# 3763.net
KiCad netlist of a schematic drawn in Altium Designer
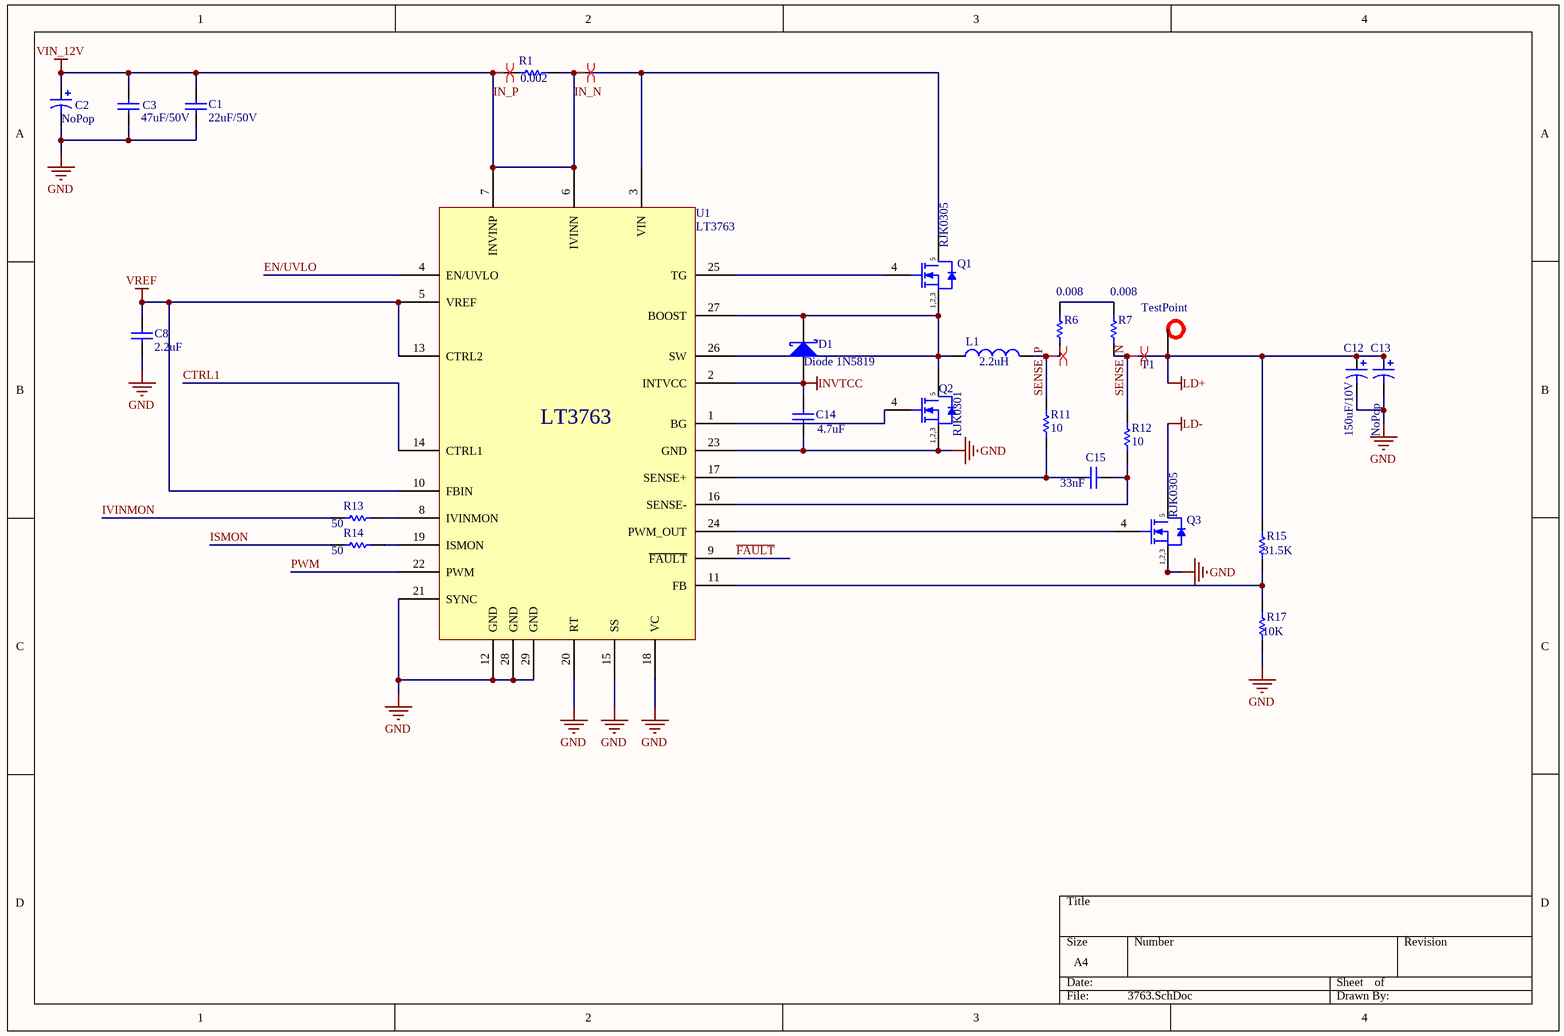
[diagram p0: 3763.SchDoc]

(export (version "E")
  (design (tool "Eeschema 10.0.6"))
  (components
    (comp (ref "C1")
      (value "22uF/50V")
      (footprint "1206[3216] - NP")
      (description "Capacitor")
      (fields (field (name "PUBLISHER") "Altium Limited"))
      (libsource (lib "Miscellaneous Devices") (part "Cap"))
    )
    (comp (ref "C2")
      (value "NoPop")
      (footprint "SMC_Altium Capacity 8*10")
      (description "Altium Electrolytic Cap")
      (fields (field (name "PUBLISHER") "Altium Limited"))
      (libsource (lib "Miscellaneous Devices") (part "Cap Pol1"))
    )
    (comp (ref "C3")
      (value "47uF/50V")
      (footprint "1206[3216] - NP")
      (description "Capacitor")
      (fields (field (name "PUBLISHER") "Altium Limited"))
      (libsource (lib "Miscellaneous Devices") (part "Cap"))
    )
    (comp (ref "C8")
      (value "2.2uF")
      (footprint "1608[0603]")
      (description "Capacitor")
      (fields (field (name "PUBLISHER") "Altium Limited"))
      (libsource (lib "Miscellaneous Devices") (part "Cap"))
    )
    (comp (ref "C12")
      (value "150uF/10V")
      (footprint "Laser-LiuXin:7343")
      (description "Tantum Cap")
      (fields (field (name "PUBLISHER") "Altium Limited"))
      (libsource (lib "Miscellaneous Devices") (part "Cap Pol1"))
    )
    (comp (ref "C13")
      (value "NoPop")
      (footprint "SMC_Altium Capacity 8*10")
      (description "Altium Electrolytic Cap")
      (fields (field (name "PUBLISHER") "Altium Limited"))
      (libsource (lib "Miscellaneous Devices") (part "Cap Pol1"))
    )
    (comp (ref "C14")
      (value "4.7uF")
      (footprint "1608[0603]")
      (description "Capacitor")
      (fields (field (name "PUBLISHER") "Altium Limited"))
      (libsource (lib "Miscellaneous Devices") (part "Cap"))
    )
    (comp (ref "C15")
      (value "33nF")
      (footprint "1608[0603]")
      (description "Capacitor")
      (fields (field (name "PUBLISHER") "Altium Limited"))
      (libsource (lib "Miscellaneous Devices") (part "Cap"))
    )
    (comp (ref "D1")
      (value "Diode 1N5819")
      (footprint "SMA")
      (description "Schottky Diode")
      (fields (field (name "PUBLISHER") "Altium Limited"))
      (libsource (lib "Miscellaneous Devices") (part "D Schottky"))
    )
    (comp (ref "L1")
      (value "2.2uH")
      (footprint "IHLP4040")
      (description "Inductor")
      (fields (field (name "Comment") "Inductor,2.2uH") (field (name "PUBLISHER") "Altium Limited"))
      (libsource (lib "Miscellaneous Devices") (part "Inductor"))
    )
    (comp (ref "Q1")
      (value "RJK0305")
      (footprint "LFPAK")
      (description "N_MOSFET")
      (fields (field (name "MANUFACTURER") "Infineon") (field (name "PARTNUMBER") "BSC160N10NS3 G"))
      (libsource (lib "Laser-LiuXin") (part "PWR_RJK030"))
    )
    (comp (ref "Q2")
      (value "RJK0301")
      (footprint "LFPAK")
      (description "N_MOSFET")
      (fields (field (name "MANUFACTURER") "Infineon") (field (name "PARTNUMBER") "BSC160N10NS3 G"))
      (libsource (lib "Laser-LiuXin") (part "PWR_RJK030"))
    )
    (comp (ref "Q3")
      (value "RJK0305")
      (footprint "LFPAK")
      (description "N_MOSFET")
      (fields (field (name "MANUFACTURER") "Infineon") (field (name "PARTNUMBER") "BSC160N10NS3 G"))
      (libsource (lib "Laser-LiuXin") (part "PWR_RJK030"))
    )
    (comp (ref "R1")
      (value "0.002")
      (footprint "2512[6432]")
      (description "Resistor")
      (fields (field (name "PUBLISHER") "Altium Limited"))
      (libsource (lib "Miscellaneous Devices") (part "Res1"))
    )
    (comp (ref "R6")
      (value "0.008")
      (footprint "2512[6432]")
      (description "Resistor")
      (fields (field (name "PUBLISHER") "Altium Limited"))
      (libsource (lib "Miscellaneous Devices") (part "Res1"))
    )
    (comp (ref "R7")
      (value "0.008")
      (footprint "2512[6432]")
      (description "Resistor")
      (fields (field (name "PUBLISHER") "Altium Limited"))
      (libsource (lib "Miscellaneous Devices") (part "Res1"))
    )
    (comp (ref "R11")
      (value "10")
      (footprint "1608[0603]")
      (description "Resistor")
      (fields (field (name "PUBLISHER") "Altium Limited"))
      (libsource (lib "Miscellaneous Devices") (part "Res1"))
    )
    (comp (ref "R12")
      (value "10")
      (footprint "1608[0603]")
      (description "Resistor")
      (fields (field (name "PUBLISHER") "Altium Limited"))
      (libsource (lib "Miscellaneous Devices") (part "Res1"))
    )
    (comp (ref "R13")
      (value "50")
      (footprint "1608[0603]")
      (description "Resistor")
      (fields (field (name "PUBLISHER") "Altium Limited"))
      (libsource (lib "Miscellaneous Devices") (part "Res1"))
    )
    (comp (ref "R14")
      (value "50")
      (footprint "1608[0603]")
      (description "Resistor")
      (fields (field (name "PUBLISHER") "Altium Limited"))
      (libsource (lib "Miscellaneous Devices") (part "Res1"))
    )
    (comp (ref "R15")
      (value "31.5K")
      (footprint "1608[0603]")
      (description "Resistor")
      (fields (field (name "PUBLISHER") "Altium Limited"))
      (libsource (lib "Miscellaneous Devices") (part "Res1"))
    )
    (comp (ref "R17")
      (value "10K")
      (footprint "1608[0603]")
      (description "Resistor")
      (fields (field (name "PUBLISHER") "Altium Limited"))
      (libsource (lib "Miscellaneous Devices") (part "Res1"))
    )
    (comp (ref "T1")
      (value "Test Point")
      (footprint "TestPoint")
      (libsource (lib "Laser-LiuXin") (part "TP"))
    )
    (comp (ref "U1")
      (value "LT3763")
      (footprint "TSOP65P640X120_HS-29N")
      (description "60V High Current   Step-Down LED Driver Controller")
      (libsource (lib "Laser-LiuXin") (part "PWR_LT3763"))
    )
  )
  (nets
    (net (code "1") (name "/CTRL1") (class "Default")
      (node (ref "U1") (pin "14") (pinfunction "CTRL1_14") (pintype "passive"))
    )
    (net (code "2") (name "/EN{slash}UVLO") (class "Default")
      (node (ref "U1") (pin "4") (pinfunction "EN/UVLO_4") (pintype "passive"))
    )
    (net (code "3") (name "/ISMON") (class "Default")
      (node (ref "R14") (pin "2") (pinfunction "2_2") (pintype "passive"))
    )
    (net (code "4") (name "/IVINMON") (class "Default")
      (node (ref "R13") (pin "2") (pinfunction "2_2") (pintype "passive"))
    )
    (net (code "5") (name "/PWM") (class "Default")
      (node (ref "U1") (pin "22") (pinfunction "PWM_22") (pintype "passive"))
    )
    (net (code "6") (name "/SENSE_P") (class "Default")
      (node (ref "L1") (pin "2") (pinfunction "2_2") (pintype "passive"))
      (node (ref "R11") (pin "2") (pinfunction "2_2") (pintype "passive"))
      (node (ref "R6") (pin "1") (pinfunction "1_1") (pintype "passive"))
    )
    (net (code "7") (name "/~{FAULT}") (class "Default")
      (node (ref "U1") (pin "9") (pinfunction "~{FAULT}_9") (pintype "passive"))
    )
    (net (code "8") (name "GND") (class "Default")
      (node (ref "C1") (pin "1") (pinfunction "1_1") (pintype "passive"))
      (node (ref "C12") (pin "2") (pinfunction "2_2") (pintype "passive"))
      (node (ref "C13") (pin "2") (pinfunction "2_2") (pintype "passive"))
      (node (ref "C14") (pin "1") (pinfunction "1_1") (pintype "passive"))
      (node (ref "C2") (pin "2") (pinfunction "2_2") (pintype "passive"))
      (node (ref "C3") (pin "1") (pinfunction "1_1") (pintype "passive"))
      (node (ref "C8") (pin "1") (pinfunction "1_1") (pintype "passive"))
      (node (ref "Q2") (pin "1") (pinfunction "SOURCE_1") (pintype "passive"))
      (node (ref "Q2") (pin "2") (pinfunction "SOURCE_2") (pintype "passive"))
      (node (ref "Q2") (pin "3") (pinfunction "SOURCE_3") (pintype "passive"))
      (node (ref "Q3") (pin "1") (pinfunction "SOURCE_1") (pintype "passive"))
      (node (ref "Q3") (pin "2") (pinfunction "SOURCE_2") (pintype "passive"))
      (node (ref "Q3") (pin "3") (pinfunction "SOURCE_3") (pintype "passive"))
      (node (ref "R17") (pin "2") (pinfunction "2_2") (pintype "passive"))
      (node (ref "U1") (pin "12") (pinfunction "GND_12") (pintype "passive"))
      (node (ref "U1") (pin "15") (pinfunction "SS_15") (pintype "passive"))
      (node (ref "U1") (pin "18") (pinfunction "VC_18") (pintype "passive"))
      (node (ref "U1") (pin "20") (pinfunction "RT_20") (pintype "passive"))
      (node (ref "U1") (pin "21") (pinfunction "SYNC_21") (pintype "passive"))
      (node (ref "U1") (pin "23") (pinfunction "GND_23") (pintype "passive"))
      (node (ref "U1") (pin "28") (pinfunction "GND_28") (pintype "passive"))
      (node (ref "U1") (pin "29") (pinfunction "GND_29") (pintype "passive"))
    )
    (net (code "9") (name "INVTCC") (class "Default")
      (node (ref "C14") (pin "2") (pinfunction "2_2") (pintype "passive"))
      (node (ref "D1") (pin "1") (pinfunction "A_1") (pintype "passive"))
      (node (ref "U1") (pin "2") (pinfunction "INTVCC_2") (pintype "passive"))
    )
    (net (code "10") (name "LD+") (class "Default")
      (node (ref "C12") (pin "1") (pinfunction "1_1") (pintype "passive"))
      (node (ref "C13") (pin "1") (pinfunction "1_1") (pintype "passive"))
      (node (ref "R12") (pin "2") (pinfunction "2_2") (pintype "passive"))
      (node (ref "R15") (pin "1") (pinfunction "1_1") (pintype "passive"))
      (node (ref "R7") (pin "1") (pinfunction "1_1") (pintype "passive"))
      (node (ref "T1") (pin "1") (pinfunction "TP_1") (pintype "passive"))
    )
    (net (code "11") (name "LD-") (class "Default")
      (node (ref "Q3") (pin "5") (pinfunction "DRAIN_5") (pintype "passive"))
    )
    (net (code "12") (name "Net-(D1-K)") (class "Default")
      (node (ref "D1") (pin "2") (pinfunction "K_2") (pintype "passive"))
      (node (ref "L1") (pin "1") (pinfunction "1_1") (pintype "passive"))
      (node (ref "Q1") (pin "1") (pinfunction "SOURCE_1") (pintype "passive"))
      (node (ref "Q1") (pin "2") (pinfunction "SOURCE_2") (pintype "passive"))
      (node (ref "Q1") (pin "3") (pinfunction "SOURCE_3") (pintype "passive"))
      (node (ref "Q2") (pin "5") (pinfunction "DRAIN_5") (pintype "passive"))
      (node (ref "U1") (pin "26") (pinfunction "SW_26") (pintype "passive"))
      (node (ref "U1") (pin "27") (pinfunction "BOOST_27") (pintype "passive"))
    )
    (net (code "13") (name "Net-(Q1-GATE)") (class "Default")
      (node (ref "Q1") (pin "4") (pinfunction "GATE_4") (pintype "passive"))
      (node (ref "U1") (pin "25") (pinfunction "TG_25") (pintype "passive"))
    )
    (net (code "14") (name "Net-(Q2-GATE)") (class "Default")
      (node (ref "Q2") (pin "4") (pinfunction "GATE_4") (pintype "passive"))
      (node (ref "U1") (pin "1") (pinfunction "BG_1") (pintype "passive"))
    )
    (net (code "15") (name "Net-(Q3-GATE)") (class "Default")
      (node (ref "Q3") (pin "4") (pinfunction "GATE_4") (pintype "passive"))
      (node (ref "U1") (pin "24") (pinfunction "PWM_OUT_24") (pintype "passive"))
    )
    (net (code "16") (name "Net-(R6-Pad2)") (class "Default")
      (node (ref "R6") (pin "2") (pinfunction "2_2") (pintype "passive"))
      (node (ref "R7") (pin "2") (pinfunction "2_2") (pintype "passive"))
    )
    (net (code "17") (name "Net-(U1-FB)") (class "Default")
      (node (ref "R15") (pin "2") (pinfunction "2_2") (pintype "passive"))
      (node (ref "R17") (pin "1") (pinfunction "1_1") (pintype "passive"))
      (node (ref "U1") (pin "11") (pinfunction "FB_11") (pintype "passive"))
    )
    (net (code "18") (name "Net-(U1-ISMON)") (class "Default")
      (node (ref "R14") (pin "1") (pinfunction "1_1") (pintype "passive"))
      (node (ref "U1") (pin "19") (pinfunction "ISMON_19") (pintype "passive"))
    )
    (net (code "19") (name "Net-(U1-IVINMON)") (class "Default")
      (node (ref "R13") (pin "1") (pinfunction "1_1") (pintype "passive"))
      (node (ref "U1") (pin "8") (pinfunction "IVINMON_8") (pintype "passive"))
    )
    (net (code "20") (name "Net-(U1-SENSE+)") (class "Default")
      (node (ref "C15") (pin "1") (pinfunction "1_1") (pintype "passive"))
      (node (ref "R11") (pin "1") (pinfunction "1_1") (pintype "passive"))
      (node (ref "U1") (pin "17") (pinfunction "SENSE+_17") (pintype "passive"))
    )
    (net (code "21") (name "Net-(U1-SENSE-)") (class "Default")
      (node (ref "C15") (pin "2") (pinfunction "2_2") (pintype "passive"))
      (node (ref "R12") (pin "1") (pinfunction "1_1") (pintype "passive"))
      (node (ref "U1") (pin "16") (pinfunction "SENSE-_16") (pintype "passive"))
    )
    (net (code "22") (name "VIN_12V") (class "Default")
      (node (ref "C1") (pin "2") (pinfunction "2_2") (pintype "passive"))
      (node (ref "C2") (pin "1") (pinfunction "1_1") (pintype "passive"))
      (node (ref "C3") (pin "2") (pinfunction "2_2") (pintype "passive"))
      (node (ref "Q1") (pin "5") (pinfunction "DRAIN_5") (pintype "passive"))
      (node (ref "R1") (pin "1") (pinfunction "1_1") (pintype "passive"))
      (node (ref "R1") (pin "2") (pinfunction "2_2") (pintype "passive"))
      (node (ref "U1") (pin "3") (pinfunction "VIN_3") (pintype "passive"))
      (node (ref "U1") (pin "6") (pinfunction "IVINN_6") (pintype "passive"))
      (node (ref "U1") (pin "7") (pinfunction "INVINP_7") (pintype "passive"))
    )
    (net (code "23") (name "VREF") (class "Default")
      (node (ref "C8") (pin "2") (pinfunction "2_2") (pintype "passive"))
      (node (ref "U1") (pin "10") (pinfunction "FBIN_10") (pintype "passive"))
      (node (ref "U1") (pin "13") (pinfunction "CTRL2_13") (pintype "passive"))
      (node (ref "U1") (pin "5") (pinfunction "VREF_5") (pintype "passive"))
    )
  )
)
